# actuator.net
KiCad netlist of a schematic drawn in EAGLE
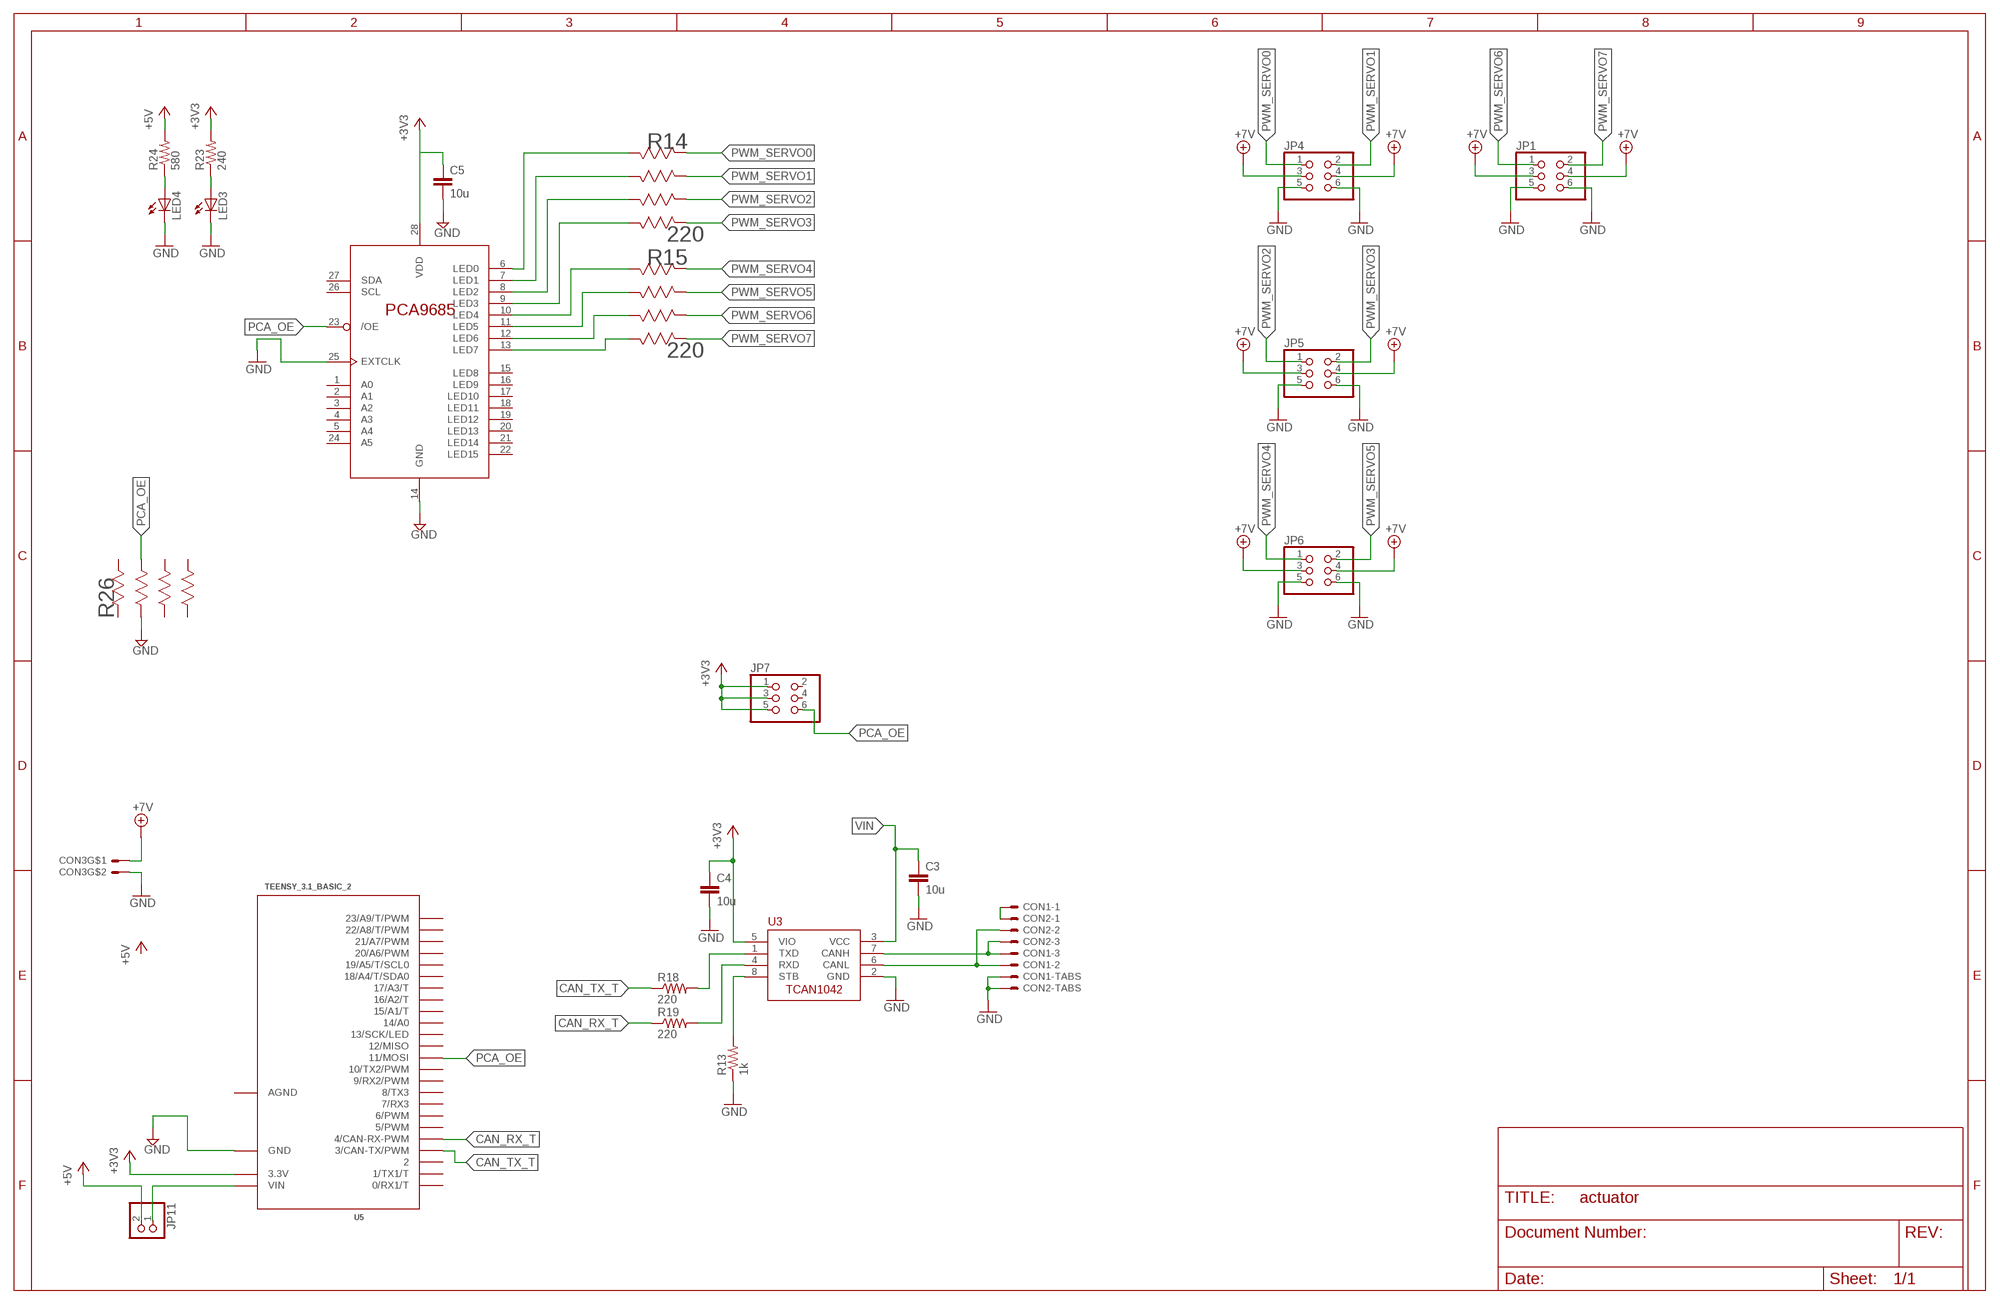
[diagram p0: schematic, sheet 1]

(export (version "E")
  (design (tool "Eeschema 10.0.6"))
  (components
    (comp (ref "C3")
      (value "10u")
      (footprint "eagle-import:C0805")
      (libsource (lib "eagle-import") (part "C-EUC0805"))
    )
    (comp (ref "C4")
      (value "10u")
      (footprint "eagle-import:C0805")
      (libsource (lib "eagle-import") (part "C-EUC0805"))
    )
    (comp (ref "C5")
      (value "10u")
      (footprint "eagle-import:C0805")
      (libsource (lib "eagle-import") (part "C-EUC0805"))
    )
    (comp (ref "CON1")
      (value "SM03B-GHS-TB")
      (footprint "eagle-import:SM03B-GHS-TB")
      (libsource (lib "eagle-import") (part "SM03B-GHS-TB"))
    )
    (comp (ref "CON2")
      (value "SM03B-GHS-TB")
      (footprint "eagle-import:SM03B-GHS-TB")
      (libsource (lib "eagle-import") (part "SM03B-GHS-TB"))
    )
    (comp (ref "CON3")
      (value "MOLEX_5566-2")
      (footprint "eagle-import:5566-2")
      (libsource (lib "eagle-import") (part "MOLEX_5566-2"))
    )
    (comp (ref "JP1")
      (value "PINHD-2X3")
      (footprint "eagle-import:2X03")
      (libsource (lib "eagle-import") (part "PINHD-2X3"))
    )
    (comp (ref "JP4")
      (value "PINHD-2X3")
      (footprint "eagle-import:2X03")
      (libsource (lib "eagle-import") (part "PINHD-2X3"))
    )
    (comp (ref "JP5")
      (value "PINHD-2X3")
      (footprint "eagle-import:2X03")
      (libsource (lib "eagle-import") (part "PINHD-2X3"))
    )
    (comp (ref "JP6")
      (value "PINHD-2X3")
      (footprint "eagle-import:2X03")
      (libsource (lib "eagle-import") (part "PINHD-2X3"))
    )
    (comp (ref "JP7")
      (value "PINHD-2X3")
      (footprint "eagle-import:2X03")
      (libsource (lib "eagle-import") (part "PINHD-2X3"))
    )
    (comp (ref "JP11")
      (value "PINHD-1X2")
      (footprint "eagle-import:1X02")
      (libsource (lib "eagle-import") (part "PINHD-1X2"))
    )
    (comp (ref "LED3")
      (value "LEDCHIPLED_1206")
      (footprint "eagle-import:CHIPLED_1206")
      (libsource (lib "eagle-import") (part "LEDCHIPLED_1206"))
    )
    (comp (ref "LED4")
      (value "LEDCHIPLED_1206")
      (footprint "eagle-import:CHIPLED_1206")
      (libsource (lib "eagle-import") (part "LEDCHIPLED_1206"))
    )
    (comp (ref "R13")
      (value "1k")
      (footprint "eagle-import:R0805")
      (libsource (lib "eagle-import") (part "R-US_R0805"))
    )
    (comp (ref "R14")
      (value "220")
      (footprint "eagle-import:EXBV8V-M")
      (fields (field (name "MANUFACTURER_PART_NUMBER") "EXBV8V221JV"))
      (libsource (lib "eagle-import") (part "EXB-V8V221JVEXBV8V-M"))
    )
    (comp (ref "R15")
      (value "220")
      (footprint "eagle-import:EXBV8V-M")
      (fields (field (name "MANUFACTURER_PART_NUMBER") "EXBV8V221JV"))
      (libsource (lib "eagle-import") (part "EXB-V8V221JVEXBV8V-M"))
    )
    (comp (ref "R18")
      (value "220")
      (footprint "eagle-import:R0805")
      (libsource (lib "eagle-import") (part "R-US_R0805"))
    )
    (comp (ref "R19")
      (value "220")
      (footprint "eagle-import:R0805")
      (libsource (lib "eagle-import") (part "R-US_R0805"))
    )
    (comp (ref "R23")
      (value "240")
      (footprint "eagle-import:R1206")
      (libsource (lib "eagle-import") (part "R-US_R1206"))
    )
    (comp (ref "R24")
      (value "580")
      (footprint "eagle-import:R1206")
      (libsource (lib "eagle-import") (part "R-US_R1206"))
    )
    (comp (ref "R26")
      (value "10k")
      (footprint "eagle-import:EXBV8V-M")
      (fields (field (name "MANUFACTURER_PART_NUMBER") "EXBV8V221JV"))
      (libsource (lib "eagle-import") (part "EXB-V8V221JVEXBV8V-M"))
    )
    (comp (ref "U3")
      (value "TCAN1042HVDR")
      (footprint "eagle-import:SO-8")
      (libsource (lib "eagle-import") (part "TCAN1042HVDR"))
    )
    (comp (ref "U4")
      (value "PCA9685PW")
      (footprint "eagle-import:TSSOP28")
      (libsource (lib "eagle-import") (part "PCA9685PW"))
    )
    (comp (ref "U5")
      (value "TEENSY_3.1_BASIC_2")
      (footprint "eagle-import:TEENSY_3.1_BASIC_2")
      (libsource (lib "eagle-import") (part "TEENSY_3.1_BASIC_2"))
    )
  )
  (nets
    (net (code "1") (name "+3V3") (class "Default")
      (node (ref "C4") (pin "1") (pinfunction "1_1") (pintype "passive"))
      (node (ref "C5") (pin "1") (pinfunction "1_1") (pintype "passive"))
      (node (ref "JP7") (pin "1") (pinfunction "1_1") (pintype "passive"))
      (node (ref "JP7") (pin "3") (pinfunction "3_3") (pintype "passive"))
      (node (ref "JP7") (pin "5") (pinfunction "5_5") (pintype "passive"))
      (node (ref "R23") (pin "2") (pinfunction "2_2") (pintype "passive"))
      (node (ref "U3") (pin "5") (pinfunction "VIO_5") (pintype "bidirectional"))
      (node (ref "U4") (pin "28") (pinfunction "VDD_28") (pintype "power_in"))
      (node (ref "U5") (pin "3.3V") (pinfunction "3.3V_3.3V") (pintype "power_in"))
    )
    (net (code "2") (name "+5V") (class "Default")
      (node (ref "JP11") (pin "2") (pinfunction "2_2") (pintype "passive"))
      (node (ref "R24") (pin "2") (pinfunction "2_2") (pintype "passive"))
    )
    (net (code "3") (name "+7V") (class "Default")
      (node (ref "CON3") (pin "1") (pinfunction "S_1") (pintype "passive"))
      (node (ref "JP1") (pin "3") (pinfunction "3_3") (pintype "passive"))
      (node (ref "JP1") (pin "4") (pinfunction "4_4") (pintype "passive"))
      (node (ref "JP4") (pin "3") (pinfunction "3_3") (pintype "passive"))
      (node (ref "JP4") (pin "4") (pinfunction "4_4") (pintype "passive"))
      (node (ref "JP5") (pin "3") (pinfunction "3_3") (pintype "passive"))
      (node (ref "JP5") (pin "4") (pinfunction "4_4") (pintype "passive"))
      (node (ref "JP6") (pin "3") (pinfunction "3_3") (pintype "passive"))
      (node (ref "JP6") (pin "4") (pinfunction "4_4") (pintype "passive"))
    )
    (net (code "4") (name "/AGND") (class "Default")
      (node (ref "U5") (pin "AGND") (pinfunction "AGND_AGND") (pintype "power_in"))
    )
    (net (code "5") (name "CAN_RX_T") (class "Default")
      (node (ref "R19") (pin "1") (pinfunction "1_1") (pintype "passive"))
      (node (ref "U5") (pin "4") (pinfunction "4/CAN-RX-PWM_4") (pintype "bidirectional"))
    )
    (net (code "6") (name "CAN_TX_T") (class "Default")
      (node (ref "R18") (pin "1") (pinfunction "1_1") (pintype "passive"))
      (node (ref "U5") (pin "3") (pinfunction "3/CAN-TX/PWM_3") (pintype "bidirectional"))
    )
    (net (code "7") (name "GND") (class "Default")
      (node (ref "C3") (pin "2") (pinfunction "2_2") (pintype "passive"))
      (node (ref "C4") (pin "2") (pinfunction "2_2") (pintype "passive"))
      (node (ref "C5") (pin "2") (pinfunction "2_2") (pintype "passive"))
      (node (ref "CON1") (pin "P$4") (pinfunction "S_P$4") (pintype "passive"))
      (node (ref "CON1") (pin "P$5") (pinfunction "S_P$5") (pintype "passive"))
      (node (ref "CON2") (pin "P$4") (pinfunction "S_P$4") (pintype "passive"))
      (node (ref "CON2") (pin "P$5") (pinfunction "S_P$5") (pintype "passive"))
      (node (ref "CON3") (pin "2") (pinfunction "S_2") (pintype "passive"))
      (node (ref "JP1") (pin "5") (pinfunction "5_5") (pintype "passive"))
      (node (ref "JP1") (pin "6") (pinfunction "6_6") (pintype "passive"))
      (node (ref "JP4") (pin "5") (pinfunction "5_5") (pintype "passive"))
      (node (ref "JP4") (pin "6") (pinfunction "6_6") (pintype "passive"))
      (node (ref "JP5") (pin "5") (pinfunction "5_5") (pintype "passive"))
      (node (ref "JP5") (pin "6") (pinfunction "6_6") (pintype "passive"))
      (node (ref "JP6") (pin "5") (pinfunction "5_5") (pintype "passive"))
      (node (ref "JP6") (pin "6") (pinfunction "6_6") (pintype "passive"))
      (node (ref "LED3") (pin "C") (pinfunction "C_C") (pintype "passive"))
      (node (ref "LED4") (pin "C") (pinfunction "C_C") (pintype "passive"))
      (node (ref "R13") (pin "1") (pinfunction "1_1") (pintype "passive"))
      (node (ref "R26") (pin "2") (pinfunction "23_2") (pintype "passive"))
      (node (ref "U3") (pin "2") (pinfunction "GND_2") (pintype "bidirectional"))
      (node (ref "U4") (pin "14") (pinfunction "GND_14") (pintype "power_in"))
      (node (ref "U4") (pin "25") (pinfunction "EXTCLK_25") (pintype "input"))
      (node (ref "U5") (pin "GND") (pinfunction "GND_GND") (pintype "power_in"))
    )
    (net (code "8") (name "Net-(CON1A-S)") (class "Default")
      (node (ref "CON1") (pin "P$1") (pinfunction "S_P$1") (pintype "passive"))
      (node (ref "CON2") (pin "P$1") (pinfunction "S_P$1") (pintype "passive"))
    )
    (net (code "9") (name "Net-(CON1B-S)") (class "Default")
      (node (ref "CON1") (pin "P$2") (pinfunction "S_P$2") (pintype "passive"))
      (node (ref "CON2") (pin "P$2") (pinfunction "S_P$2") (pintype "passive"))
      (node (ref "U3") (pin "6") (pinfunction "CANL_6") (pintype "bidirectional"))
    )
    (net (code "10") (name "Net-(CON1C-S)") (class "Default")
      (node (ref "CON1") (pin "P$3") (pinfunction "S_P$3") (pintype "passive"))
      (node (ref "CON2") (pin "P$3") (pinfunction "S_P$3") (pintype "passive"))
      (node (ref "U3") (pin "7") (pinfunction "CANH_7") (pintype "bidirectional"))
    )
    (net (code "11") (name "Net-(LED3-PadA)") (class "Default")
      (node (ref "LED3") (pin "A") (pinfunction "A_A") (pintype "passive"))
      (node (ref "R23") (pin "1") (pinfunction "1_1") (pintype "passive"))
    )
    (net (code "12") (name "Net-(LED4-PadA)") (class "Default")
      (node (ref "LED4") (pin "A") (pinfunction "A_A") (pintype "passive"))
      (node (ref "R24") (pin "1") (pinfunction "1_1") (pintype "passive"))
    )
    (net (code "13") (name "Net-(R14-58)") (class "Default")
      (node (ref "R14") (pin "5") (pinfunction "58_5") (pintype "passive"))
      (node (ref "U4") (pin "9") (pinfunction "LED3_9") (pintype "bidirectional"))
    )
    (net (code "14") (name "Net-(R14-66)") (class "Default")
      (node (ref "R14") (pin "6") (pinfunction "66_6") (pintype "passive"))
      (node (ref "U4") (pin "8") (pinfunction "LED2_8") (pintype "bidirectional"))
    )
    (net (code "15") (name "Net-(R14-74)") (class "Default")
      (node (ref "R14") (pin "7") (pinfunction "74_7") (pintype "passive"))
      (node (ref "U4") (pin "7") (pinfunction "LED1_7") (pintype "bidirectional"))
    )
    (net (code "16") (name "Net-(R14-82)") (class "Default")
      (node (ref "R14") (pin "8") (pinfunction "82_8") (pintype "passive"))
      (node (ref "U4") (pin "6") (pinfunction "LED0_6") (pintype "bidirectional"))
    )
    (net (code "17") (name "Net-(R15-58)") (class "Default")
      (node (ref "R15") (pin "5") (pinfunction "58_5") (pintype "passive"))
      (node (ref "U4") (pin "13") (pinfunction "LED7_13") (pintype "bidirectional"))
    )
    (net (code "18") (name "Net-(R15-66)") (class "Default")
      (node (ref "R15") (pin "6") (pinfunction "66_6") (pintype "passive"))
      (node (ref "U4") (pin "12") (pinfunction "LED6_12") (pintype "bidirectional"))
    )
    (net (code "19") (name "Net-(R15-74)") (class "Default")
      (node (ref "R15") (pin "7") (pinfunction "74_7") (pintype "passive"))
      (node (ref "U4") (pin "11") (pinfunction "LED5_11") (pintype "bidirectional"))
    )
    (net (code "20") (name "Net-(R15-82)") (class "Default")
      (node (ref "R15") (pin "8") (pinfunction "82_8") (pintype "passive"))
      (node (ref "U4") (pin "10") (pinfunction "LED4_10") (pintype "bidirectional"))
    )
    (net (code "21") (name "Net-(U3-RXD)") (class "Default")
      (node (ref "R19") (pin "2") (pinfunction "2_2") (pintype "passive"))
      (node (ref "U3") (pin "4") (pinfunction "RXD_4") (pintype "bidirectional"))
    )
    (net (code "22") (name "Net-(U3-STB)") (class "Default")
      (node (ref "R13") (pin "2") (pinfunction "2_2") (pintype "passive"))
      (node (ref "U3") (pin "8") (pinfunction "STB_8") (pintype "bidirectional"))
    )
    (net (code "23") (name "Net-(U3-TXD)") (class "Default")
      (node (ref "R18") (pin "2") (pinfunction "2_2") (pintype "passive"))
      (node (ref "U3") (pin "1") (pinfunction "TXD_1") (pintype "bidirectional"))
    )
    (net (code "24") (name "PCA_OE") (class "Default")
      (node (ref "JP7") (pin "6") (pinfunction "6_6") (pintype "passive"))
      (node (ref "R26") (pin "7") (pinfunction "74_7") (pintype "passive"))
      (node (ref "U4") (pin "23") (pinfunction "/OE_23") (pintype "bidirectional"))
      (node (ref "U5") (pin "11") (pinfunction "11/MOSI_11") (pintype "bidirectional"))
    )
    (net (code "25") (name "PWM_SERVO0") (class "Default")
      (node (ref "JP4") (pin "1") (pinfunction "1_1") (pintype "passive"))
      (node (ref "R14") (pin "1") (pinfunction "11_1") (pintype "passive"))
    )
    (net (code "26") (name "PWM_SERVO1") (class "Default")
      (node (ref "JP4") (pin "2") (pinfunction "2_2") (pintype "passive"))
      (node (ref "R14") (pin "2") (pinfunction "23_2") (pintype "passive"))
    )
    (net (code "27") (name "PWM_SERVO2") (class "Default")
      (node (ref "JP5") (pin "1") (pinfunction "1_1") (pintype "passive"))
      (node (ref "R14") (pin "3") (pinfunction "35_3") (pintype "passive"))
    )
    (net (code "28") (name "PWM_SERVO3") (class "Default")
      (node (ref "JP5") (pin "2") (pinfunction "2_2") (pintype "passive"))
      (node (ref "R14") (pin "4") (pinfunction "47_4") (pintype "passive"))
    )
    (net (code "29") (name "PWM_SERVO4") (class "Default")
      (node (ref "JP6") (pin "1") (pinfunction "1_1") (pintype "passive"))
      (node (ref "R15") (pin "1") (pinfunction "11_1") (pintype "passive"))
    )
    (net (code "30") (name "PWM_SERVO5") (class "Default")
      (node (ref "JP6") (pin "2") (pinfunction "2_2") (pintype "passive"))
      (node (ref "R15") (pin "2") (pinfunction "23_2") (pintype "passive"))
    )
    (net (code "31") (name "PWM_SERVO6") (class "Default")
      (node (ref "JP1") (pin "1") (pinfunction "1_1") (pintype "passive"))
      (node (ref "R15") (pin "3") (pinfunction "35_3") (pintype "passive"))
    )
    (net (code "32") (name "PWM_SERVO7") (class "Default")
      (node (ref "JP1") (pin "2") (pinfunction "2_2") (pintype "passive"))
      (node (ref "R15") (pin "4") (pinfunction "47_4") (pintype "passive"))
    )
    (net (code "33") (name "VIN") (class "Default")
      (node (ref "C3") (pin "1") (pinfunction "1_1") (pintype "passive"))
      (node (ref "JP11") (pin "1") (pinfunction "1_1") (pintype "passive"))
      (node (ref "U3") (pin "3") (pinfunction "VCC_3") (pintype "bidirectional"))
      (node (ref "U5") (pin "VIN") (pinfunction "VIN_VIN") (pintype "power_in"))
    )
    (net (code "34") (name "unconnected-(JP7-Pad2)") (class "Default")
      (node (ref "JP7") (pin "2") (pinfunction "2_2") (pintype "passive"))
    )
    (net (code "35") (name "unconnected-(JP7-Pad4)") (class "Default")
      (node (ref "JP7") (pin "4") (pinfunction "4_4") (pintype "passive"))
    )
    (net (code "36") (name "unconnected-(R26-11-Pad1)") (class "Default")
      (node (ref "R26") (pin "1") (pinfunction "11_1") (pintype "passive"))
    )
    (net (code "37") (name "unconnected-(R26-35-Pad3)") (class "Default")
      (node (ref "R26") (pin "3") (pinfunction "35_3") (pintype "passive"))
    )
    (net (code "38") (name "unconnected-(R26-47-Pad4)") (class "Default")
      (node (ref "R26") (pin "4") (pinfunction "47_4") (pintype "passive"))
    )
    (net (code "39") (name "unconnected-(R26-58-Pad5)") (class "Default")
      (node (ref "R26") (pin "5") (pinfunction "58_5") (pintype "passive"))
    )
    (net (code "40") (name "unconnected-(R26-66-Pad6)") (class "Default")
      (node (ref "R26") (pin "6") (pinfunction "66_6") (pintype "passive"))
    )
    (net (code "41") (name "unconnected-(R26-82-Pad8)") (class "Default")
      (node (ref "R26") (pin "8") (pinfunction "82_8") (pintype "passive"))
    )
    (net (code "42") (name "unconnected-(U4-A0-Pad1)") (class "Default")
      (node (ref "U4") (pin "1") (pinfunction "A0_1") (pintype "bidirectional"))
    )
    (net (code "43") (name "unconnected-(U4-A1-Pad2)") (class "Default")
      (node (ref "U4") (pin "2") (pinfunction "A1_2") (pintype "bidirectional"))
    )
    (net (code "44") (name "unconnected-(U4-A2-Pad3)") (class "Default")
      (node (ref "U4") (pin "3") (pinfunction "A2_3") (pintype "bidirectional"))
    )
    (net (code "45") (name "unconnected-(U4-A3-Pad4)") (class "Default")
      (node (ref "U4") (pin "4") (pinfunction "A3_4") (pintype "bidirectional"))
    )
    (net (code "46") (name "unconnected-(U4-A4-Pad5)") (class "Default")
      (node (ref "U4") (pin "5") (pinfunction "A4_5") (pintype "bidirectional"))
    )
    (net (code "47") (name "unconnected-(U4-A5-Pad24)") (class "Default")
      (node (ref "U4") (pin "24") (pinfunction "A5_24") (pintype "bidirectional"))
    )
    (net (code "48") (name "unconnected-(U4-LED8-Pad15)") (class "Default")
      (node (ref "U4") (pin "15") (pinfunction "LED8_15") (pintype "bidirectional"))
    )
    (net (code "49") (name "unconnected-(U4-LED9-Pad16)") (class "Default")
      (node (ref "U4") (pin "16") (pinfunction "LED9_16") (pintype "bidirectional"))
    )
    (net (code "50") (name "unconnected-(U4-LED10-Pad17)") (class "Default")
      (node (ref "U4") (pin "17") (pinfunction "LED10_17") (pintype "bidirectional"))
    )
    (net (code "51") (name "unconnected-(U4-LED11-Pad18)") (class "Default")
      (node (ref "U4") (pin "18") (pinfunction "LED11_18") (pintype "bidirectional"))
    )
    (net (code "52") (name "unconnected-(U4-LED12-Pad19)") (class "Default")
      (node (ref "U4") (pin "19") (pinfunction "LED12_19") (pintype "bidirectional"))
    )
    (net (code "53") (name "unconnected-(U4-LED13-Pad20)") (class "Default")
      (node (ref "U4") (pin "20") (pinfunction "LED13_20") (pintype "bidirectional"))
    )
    (net (code "54") (name "unconnected-(U4-LED14-Pad21)") (class "Default")
      (node (ref "U4") (pin "21") (pinfunction "LED14_21") (pintype "bidirectional"))
    )
    (net (code "55") (name "unconnected-(U4-LED15-Pad22)") (class "Default")
      (node (ref "U4") (pin "22") (pinfunction "LED15_22") (pintype "bidirectional"))
    )
    (net (code "56") (name "unconnected-(U4-SCL-Pad26)") (class "Default")
      (node (ref "U4") (pin "26") (pinfunction "SCL_26") (pintype "bidirectional"))
    )
    (net (code "57") (name "unconnected-(U4-SDA-Pad27)") (class "Default")
      (node (ref "U4") (pin "27") (pinfunction "SDA_27") (pintype "bidirectional"))
    )
    (net (code "58") (name "unconnected-(U5-0{slash}RX1{slash}T-Pad0)") (class "Default")
      (node (ref "U5") (pin "0") (pinfunction "0/RX1/T_0") (pintype "bidirectional"))
    )
    (net (code "59") (name "unconnected-(U5-1{slash}TX1{slash}T-Pad1)") (class "Default")
      (node (ref "U5") (pin "1") (pinfunction "1/TX1/T_1") (pintype "bidirectional"))
    )
    (net (code "60") (name "unconnected-(U5-5{slash}PWM-Pad5)") (class "Default")
      (node (ref "U5") (pin "5") (pinfunction "5/PWM_5") (pintype "bidirectional"))
    )
    (net (code "61") (name "unconnected-(U5-6{slash}PWM-Pad6)") (class "Default")
      (node (ref "U5") (pin "6") (pinfunction "6/PWM_6") (pintype "bidirectional"))
    )
    (net (code "62") (name "unconnected-(U5-7{slash}RX3-Pad7)") (class "Default")
      (node (ref "U5") (pin "7") (pinfunction "7/RX3_7") (pintype "bidirectional"))
    )
    (net (code "63") (name "unconnected-(U5-8{slash}TX3-Pad8)") (class "Default")
      (node (ref "U5") (pin "8") (pinfunction "8/TX3_8") (pintype "bidirectional"))
    )
    (net (code "64") (name "unconnected-(U5-9{slash}RX2{slash}PWM-Pad9)") (class "Default")
      (node (ref "U5") (pin "9") (pinfunction "9/RX2/PWM_9") (pintype "bidirectional"))
    )
    (net (code "65") (name "unconnected-(U5-10{slash}TX2{slash}PWM-Pad10)") (class "Default")
      (node (ref "U5") (pin "10") (pinfunction "10/TX2/PWM_10") (pintype "bidirectional"))
    )
    (net (code "66") (name "unconnected-(U5-12{slash}MISO-Pad12)") (class "Default")
      (node (ref "U5") (pin "12") (pinfunction "12/MISO_12") (pintype "bidirectional"))
    )
    (net (code "67") (name "unconnected-(U5-13{slash}SCK{slash}LED-Pad13)") (class "Default")
      (node (ref "U5") (pin "13") (pinfunction "13/SCK/LED_13") (pintype "bidirectional"))
    )
    (net (code "68") (name "unconnected-(U5-15{slash}A1{slash}T-Pad15{slash}A1)") (class "Default")
      (node (ref "U5") (pin "15/A1") (pinfunction "15/A1/T_15/A1") (pintype "bidirectional"))
    )
    (net (code "69") (name "unconnected-(U5-16{slash}A2{slash}T-Pad16{slash}A2)") (class "Default")
      (node (ref "U5") (pin "16/A2") (pinfunction "16/A2/T_16/A2") (pintype "bidirectional"))
    )
    (net (code "70") (name "unconnected-(U5-17{slash}A3{slash}T-Pad17{slash}A3)") (class "Default")
      (node (ref "U5") (pin "17/A3") (pinfunction "17/A3/T_17/A3") (pintype "bidirectional"))
    )
    (net (code "71") (name "unconnected-(U5-18{slash}A4{slash}T{slash}SDA0-Pad18{slash}A4)") (class "Default")
      (node (ref "U5") (pin "18/A4") (pinfunction "18/A4/T/SDA0_18/A4") (pintype "bidirectional"))
    )
    (net (code "72") (name "unconnected-(U5-19{slash}A5{slash}T{slash}SCL0-Pad19{slash}A5)") (class "Default")
      (node (ref "U5") (pin "19/A5") (pinfunction "19/A5/T/SCL0_19/A5") (pintype "bidirectional"))
    )
    (net (code "73") (name "unconnected-(U5-20{slash}A6{slash}PWM-Pad20{slash}A6)") (class "Default")
      (node (ref "U5") (pin "20/A6") (pinfunction "20/A6/PWM_20/A6") (pintype "bidirectional"))
    )
    (net (code "74") (name "unconnected-(U5-21{slash}A7{slash}PWM-Pad21{slash}A7)") (class "Default")
      (node (ref "U5") (pin "21/A7") (pinfunction "21/A7/PWM_21/A7") (pintype "bidirectional"))
    )
    (net (code "75") (name "unconnected-(U5-22{slash}A8{slash}T{slash}PWM-Pad22{slash}A8)") (class "Default")
      (node (ref "U5") (pin "22/A8") (pinfunction "22/A8/T/PWM_22/A8") (pintype "bidirectional"))
    )
    (net (code "76") (name "unconnected-(U5-23{slash}A9{slash}T{slash}PWM-Pad23{slash}A9)") (class "Default")
      (node (ref "U5") (pin "23/A9") (pinfunction "23/A9/T/PWM_23/A9") (pintype "bidirectional"))
    )
    (net (code "77") (name "unconnected-(U5-Pad2)") (class "Default")
      (node (ref "U5") (pin "2") (pinfunction "2_2") (pintype "bidirectional"))
    )
    (net (code "78") (name "unconnected-(U5-Pad14{slash}A0)") (class "Default")
      (node (ref "U5") (pin "14/A0") (pinfunction "14/A0_14/A0") (pintype "bidirectional"))
    )
  )
)
